# TestV2.net
KiCad netlist of a schematic drawn in EAGLE
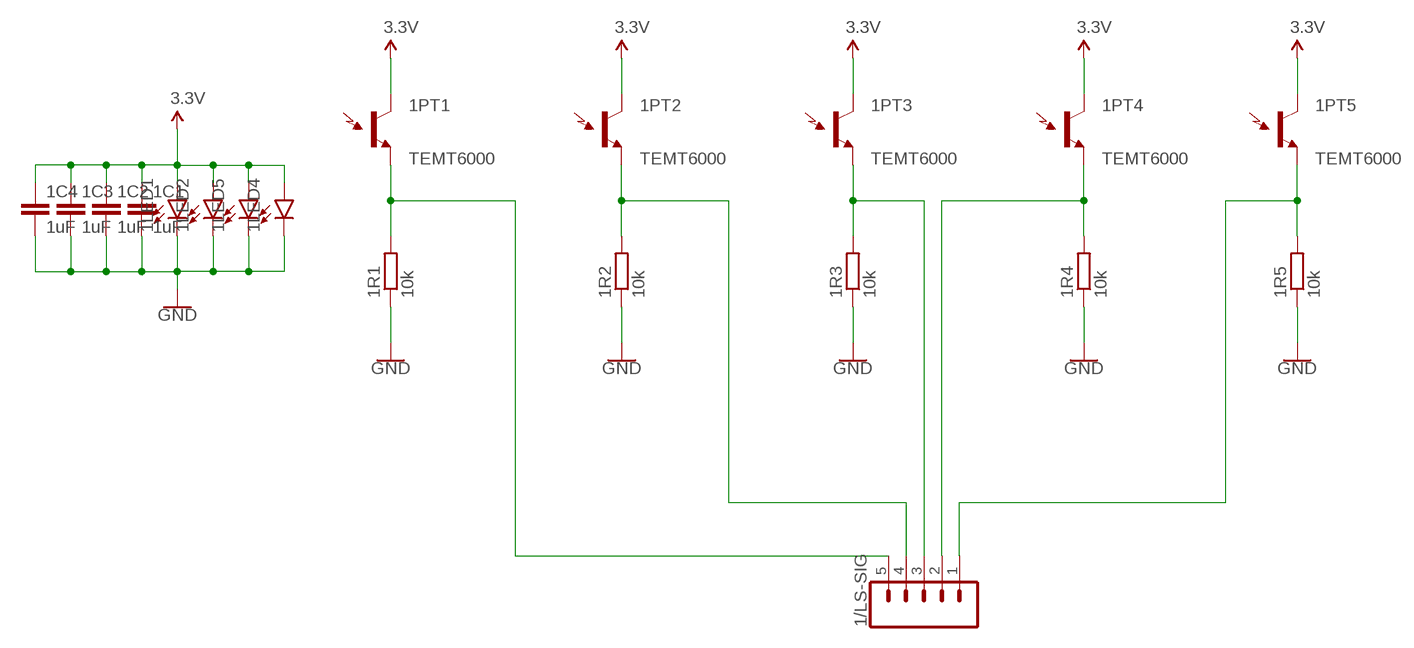
[diagram p0: schematic, sheet 1]
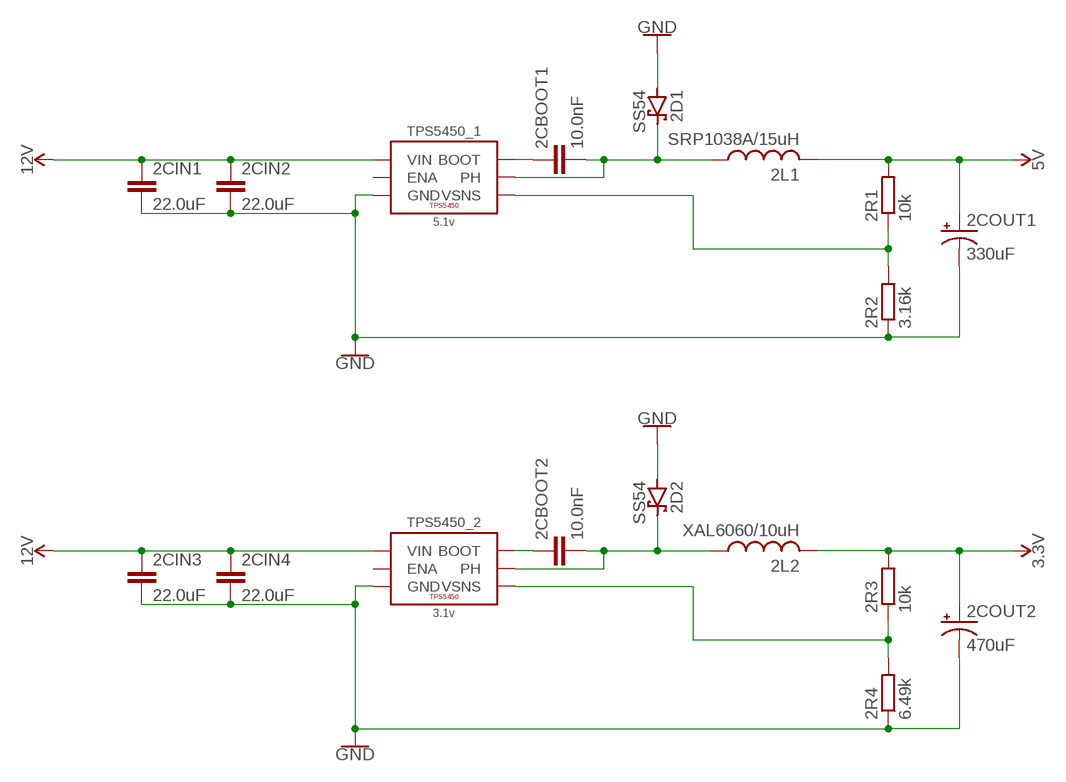
[diagram p1: schematic, sheet 2]
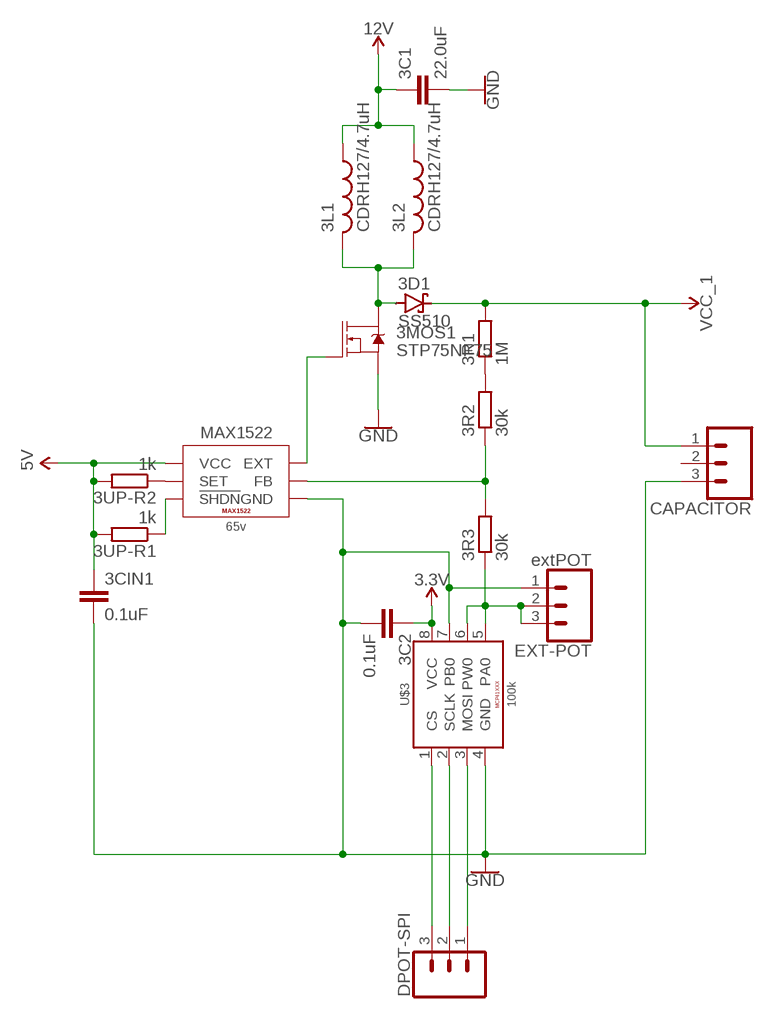
[diagram p2: schematic, sheet 3]
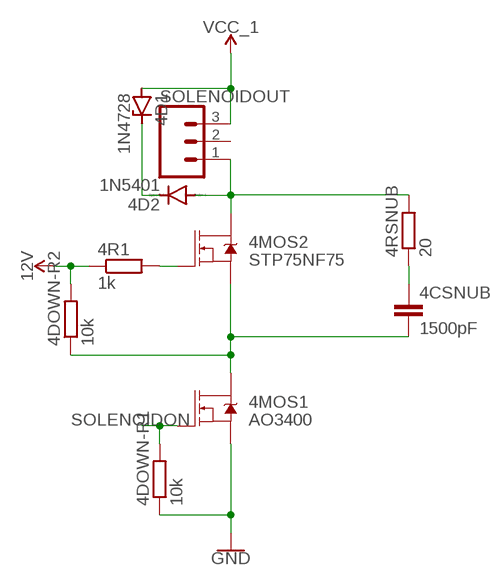
[diagram p3: schematic, sheet 4]
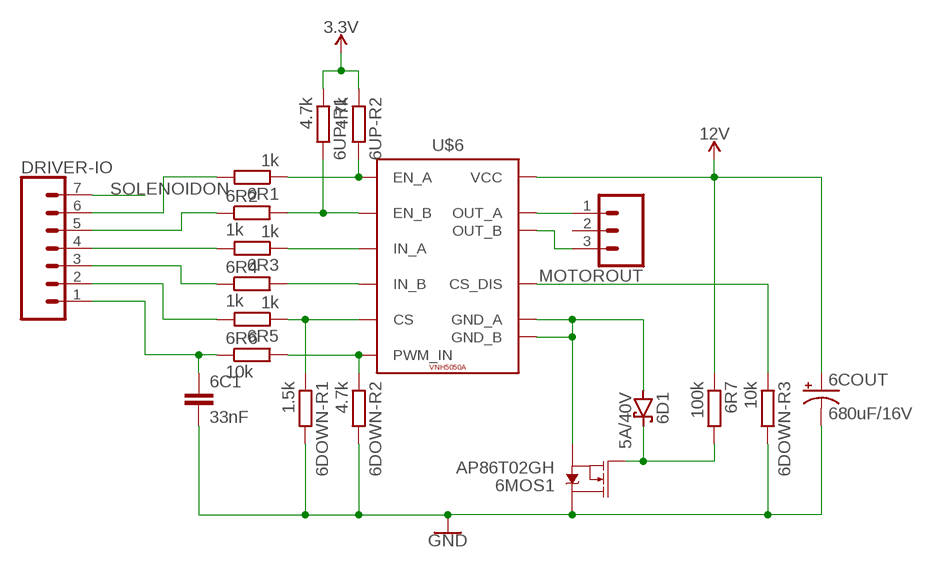
[diagram p4: schematic, sheet 5]
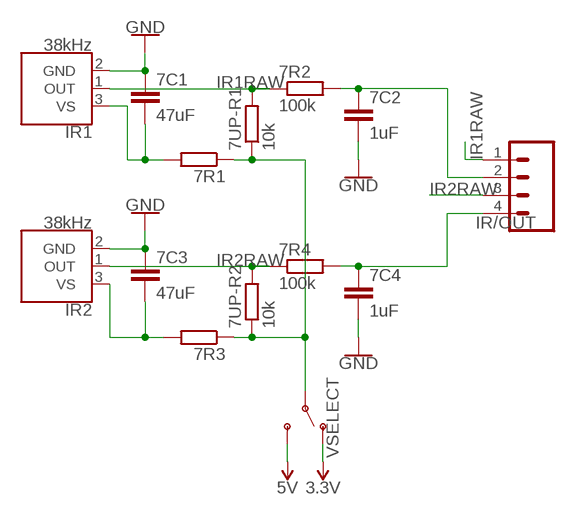
[diagram p5: schematic, sheet 6]
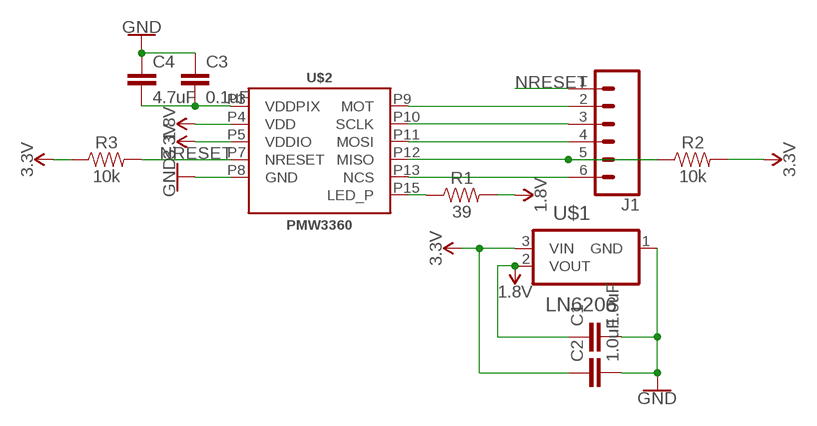
[diagram p6: schematic, sheet 7]
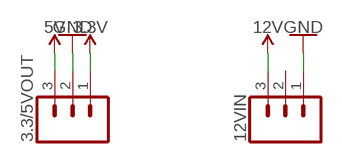
[diagram p7: schematic, sheet 8]

(export (version "E")
  (design (tool "Eeschema 10.0.6"))
  (components
    (comp (ref "1/LS-SIG")
      (value "CONN_05LOCK")
      (footprint "eagle-import:1X05_LOCK")
      (libsource (lib "eagle-import") (part "CONN_05LOCK"))
    )
    (comp (ref "1C1")
      (value "1uF")
      (footprint "eagle-import:C0603")
      (libsource (lib "eagle-import") (part "C-EUC0603"))
    )
    (comp (ref "1C2")
      (value "1uF")
      (footprint "eagle-import:C0603")
      (libsource (lib "eagle-import") (part "C-EUC0603"))
    )
    (comp (ref "1C3")
      (value "1uF")
      (footprint "eagle-import:C0603")
      (libsource (lib "eagle-import") (part "C-EUC0603"))
    )
    (comp (ref "1C4")
      (value "1uF")
      (footprint "eagle-import:C0603")
      (libsource (lib "eagle-import") (part "C-EUC0603"))
    )
    (comp (ref "1LED1")
      (value "3528LED")
      (footprint "eagle-import:3528")
      (libsource (lib "eagle-import") (part "3528LED"))
    )
    (comp (ref "1LED2")
      (value "3528LED")
      (footprint "eagle-import:3528")
      (libsource (lib "eagle-import") (part "3528LED"))
    )
    (comp (ref "1LED4")
      (value "3528LED")
      (footprint "eagle-import:3528")
      (libsource (lib "eagle-import") (part "3528LED"))
    )
    (comp (ref "1LED5")
      (value "3528LED")
      (footprint "eagle-import:3528")
      (libsource (lib "eagle-import") (part "3528LED"))
    )
    (comp (ref "1PT1")
      (value "TEMT6000")
      (footprint "eagle-import:TEMT6000")
      (libsource (lib "eagle-import") (part "LIGHT_SENSORTEMT6000"))
    )
    (comp (ref "1PT2")
      (value "TEMT6000")
      (footprint "eagle-import:TEMT6000")
      (libsource (lib "eagle-import") (part "LIGHT_SENSORTEMT6000"))
    )
    (comp (ref "1PT3")
      (value "TEMT6000")
      (footprint "eagle-import:TEMT6000")
      (libsource (lib "eagle-import") (part "LIGHT_SENSORTEMT6000"))
    )
    (comp (ref "1PT4")
      (value "TEMT6000")
      (footprint "eagle-import:TEMT6000")
      (libsource (lib "eagle-import") (part "LIGHT_SENSORTEMT6000"))
    )
    (comp (ref "1PT5")
      (value "TEMT6000")
      (footprint "eagle-import:TEMT6000")
      (libsource (lib "eagle-import") (part "LIGHT_SENSORTEMT6000"))
    )
    (comp (ref "1R1")
      (value "10k")
      (footprint "eagle-import:R0603")
      (libsource (lib "eagle-import") (part "R-EU_R0603"))
    )
    (comp (ref "1R2")
      (value "10k")
      (footprint "eagle-import:R0603")
      (libsource (lib "eagle-import") (part "R-EU_R0603"))
    )
    (comp (ref "1R3")
      (value "10k")
      (footprint "eagle-import:R0603")
      (libsource (lib "eagle-import") (part "R-EU_R0603"))
    )
    (comp (ref "1R4")
      (value "10k")
      (footprint "eagle-import:R0603")
      (libsource (lib "eagle-import") (part "R-EU_R0603"))
    )
    (comp (ref "1R5")
      (value "10k")
      (footprint "eagle-import:R0603")
      (libsource (lib "eagle-import") (part "R-EU_R0603"))
    )
    (comp (ref "4CSNUB")
      (value "1500pF")
      (footprint "eagle-import:C0603")
      (libsource (lib "eagle-import") (part "C-EUC0603"))
    )
    (comp (ref "4D1")
      (value "1N4728")
      (footprint "eagle-import:DO41Z10")
      (libsource (lib "eagle-import") (part "1N4728"))
    )
    (comp (ref "4D2")
      (value "1N5401")
      (footprint "eagle-import:DO201-15")
      (libsource (lib "eagle-import") (part "1N5400"))
    )
    (comp (ref "4DOWN-R1")
      (value "10k")
      (footprint "eagle-import:R0603")
      (libsource (lib "eagle-import") (part "R-EU_R0603"))
    )
    (comp (ref "4DOWN-R2")
      (value "10k")
      (footprint "eagle-import:R0603")
      (libsource (lib "eagle-import") (part "R-EU_R0603"))
    )
    (comp (ref "4MOS1")
      (value "AO3400")
      (footprint "eagle-import:SOT23-3")
      (libsource (lib "eagle-import") (part "MOSFET-NCH-AO3404A"))
    )
    (comp (ref "4MOS2")
      (value "STP75NF75")
      (footprint "eagle-import:TO220V")
      (libsource (lib "eagle-import") (part "MOSFET-NCH-FQP30N06L"))
    )
    (comp (ref "4R1")
      (value "1k")
      (footprint "eagle-import:R0603")
      (libsource (lib "eagle-import") (part "R-EU_R0603"))
    )
    (comp (ref "4RSNUB")
      (value "20")
      (footprint "eagle-import:R0603")
      (libsource (lib "eagle-import") (part "R-EU_R0603"))
    )
    (comp (ref "SOLENOIDOUT")
      (value "CONN_03-SCREW-5MM")
      (footprint "eagle-import:SCREWTERMINAL-5MM-3")
      (libsource (lib "eagle-import") (part "CONN_03-SCREW-5MM"))
    )
    (comp (ref "3.3/5VOUT")
      (value "CONN_03-SCREW-5MM")
      (footprint "eagle-import:SCREWTERMINAL-5MM-3")
      (libsource (lib "eagle-import") (part "CONN_03-SCREW-5MM"))
    )
    (comp (ref "12VIN")
      (value "CONN_03-SCREW-5MM")
      (footprint "eagle-import:SCREWTERMINAL-5MM-3")
      (libsource (lib "eagle-import") (part "CONN_03-SCREW-5MM"))
    )
    (comp (ref "C1")
      (value "1.0uF")
      (footprint "eagle-import:0603")
      (libsource (lib "eagle-import") (part "1.0UF-0603-16V-10%-X7R"))
    )
    (comp (ref "C2")
      (value "1.0uF")
      (footprint "eagle-import:0603")
      (libsource (lib "eagle-import") (part "1.0UF-0603-16V-10%-X7R"))
    )
    (comp (ref "C3")
      (value "0.1uF")
      (footprint "eagle-import:0603")
      (libsource (lib "eagle-import") (part "0.1UF-0603-25V-5%"))
    )
    (comp (ref "C4")
      (value "4.7uF")
      (footprint "eagle-import:0603")
      (libsource (lib "eagle-import") (part "4.7UF-0603-6.3V-(10%)"))
    )
    (comp (ref "J1")
      (value "CONN_06LOCK")
      (footprint "eagle-import:1X06_LOCK")
      (libsource (lib "eagle-import") (part "CONN_06LOCK"))
    )
    (comp (ref "R1")
      (value "39")
      (footprint "eagle-import:0603")
      (libsource (lib "eagle-import") (part "RESISTOR0603"))
    )
    (comp (ref "R2")
      (value "10k")
      (footprint "eagle-import:0603")
      (libsource (lib "eagle-import") (part "10KOHM-0603-1/10W-1%"))
    )
    (comp (ref "R3")
      (value "10k")
      (footprint "eagle-import:0603")
      (libsource (lib "eagle-import") (part "10KOHM-0603-1/10W-1%"))
    )
    (comp (ref "U$1")
      (value "LN6206")
      (footprint "eagle-import:SOT95P237X112-3N")
      (fields (field (name "MF") "Microchip") (field (name "MP") "MCP1700T-3302E/TT"))
      (libsource (lib "eagle-import") (part "MCP1700T-3302E/TT"))
    )
    (comp (ref "U$2")
      (value "PMW3360")
      (footprint "eagle-import:PMW3360")
      (libsource (lib "eagle-import") (part "PMW3360"))
    )
    (comp (ref "2CBOOT1")
      (value "10.0nF")
      (footprint "eagle-import:C0603")
      (libsource (lib "eagle-import") (part "C-EUC0603"))
    )
    (comp (ref "2CBOOT2")
      (value "10.0nF")
      (footprint "eagle-import:C0603")
      (libsource (lib "eagle-import") (part "C-EUC0603"))
    )
    (comp (ref "2CIN1")
      (value "22.0uF")
      (footprint "eagle-import:C1210")
      (libsource (lib "eagle-import") (part "C-EUC1210"))
    )
    (comp (ref "2CIN2")
      (value "22.0uF")
      (footprint "eagle-import:C1210")
      (libsource (lib "eagle-import") (part "C-EUC1210"))
    )
    (comp (ref "2CIN3")
      (value "22.0uF")
      (footprint "eagle-import:C1210")
      (libsource (lib "eagle-import") (part "C-EUC1210"))
    )
    (comp (ref "2CIN4")
      (value "22.0uF")
      (footprint "eagle-import:C1210")
      (libsource (lib "eagle-import") (part "C-EUC1210"))
    )
    (comp (ref "2COUT1")
      (value "330uF")
      (footprint "eagle-import:D_7343-31R")
      (libsource (lib "eagle-import") (part "CPOL-USD/7343-31R"))
    )
    (comp (ref "2COUT2")
      (value "470uF")
      (footprint "eagle-import:D_7343-31R")
      (libsource (lib "eagle-import") (part "CPOL-USD/7343-31R"))
    )
    (comp (ref "2D1")
      (value "SS54")
      (footprint "eagle-import:SMB")
      (libsource (lib "eagle-import") (part "SCHOTTKY-DIODESMD"))
    )
    (comp (ref "2D2")
      (value "SS54")
      (footprint "eagle-import:SMB")
      (libsource (lib "eagle-import") (part "SCHOTTKY-DIODESMD"))
    )
    (comp (ref "2L1")
      (value "SRP1038A/15uH")
      (footprint "eagle-import:SRP1038A")
      (libsource (lib "eagle-import") (part "SRP1038A"))
    )
    (comp (ref "2L2")
      (value "XAL6060/10uH")
      (footprint "eagle-import:XAL6060")
      (libsource (lib "eagle-import") (part "XAL6060"))
    )
    (comp (ref "2R1")
      (value "10k")
      (footprint "eagle-import:R0603")
      (libsource (lib "eagle-import") (part "R-EU_R0603"))
    )
    (comp (ref "2R2")
      (value "3.16k")
      (footprint "eagle-import:R0603")
      (libsource (lib "eagle-import") (part "R-EU_R0603"))
    )
    (comp (ref "2R3")
      (value "10k")
      (footprint "eagle-import:R0603")
      (libsource (lib "eagle-import") (part "R-EU_R0603"))
    )
    (comp (ref "2R4")
      (value "6.49k")
      (footprint "eagle-import:R0603")
      (libsource (lib "eagle-import") (part "R-EU_R0603"))
    )
    (comp (ref "TPS5450_1")
      (value "5.1v")
      (footprint "eagle-import:POWERPAD-SOIC-8")
      (libsource (lib "eagle-import") (part "TPS5450"))
    )
    (comp (ref "TPS5450_2")
      (value "3.1v")
      (footprint "eagle-import:POWERPAD-SOIC-8")
      (libsource (lib "eagle-import") (part "TPS5450"))
    )
    (comp (ref "3C1")
      (value "22.0uF")
      (footprint "eagle-import:C1210")
      (libsource (lib "eagle-import") (part "C-EUC1210"))
    )
    (comp (ref "3C2")
      (value "0.1uF")
      (footprint "eagle-import:C0603")
      (libsource (lib "eagle-import") (part "C-EUC0603"))
    )
    (comp (ref "3CIN1")
      (value "0.1uF")
      (footprint "eagle-import:C0603")
      (libsource (lib "eagle-import") (part "C-EUC0603"))
    )
    (comp (ref "3D1")
      (value "SS510")
      (footprint "eagle-import:SMB")
      (libsource (lib "eagle-import") (part "SCHOTTKY-DIODESMD"))
    )
    (comp (ref "3L1")
      (value "CDRH127/4.7uH")
      (footprint "eagle-import:127")
      (libsource (lib "eagle-import") (part "CDRH127"))
    )
    (comp (ref "3L2")
      (value "CDRH127/4.7uH")
      (footprint "eagle-import:127")
      (libsource (lib "eagle-import") (part "CDRH127"))
    )
    (comp (ref "3MOS1")
      (value "STP75NF75")
      (footprint "eagle-import:TO220V")
      (libsource (lib "eagle-import") (part "MOSFET-NCH-FQP30N06L"))
    )
    (comp (ref "3R1")
      (value "1M")
      (footprint "eagle-import:R0603")
      (libsource (lib "eagle-import") (part "R-EU_R0603"))
    )
    (comp (ref "3R2")
      (value "30k")
      (footprint "eagle-import:R0603")
      (libsource (lib "eagle-import") (part "R-EU_R0603"))
    )
    (comp (ref "3R3")
      (value "30k")
      (footprint "eagle-import:R0603")
      (libsource (lib "eagle-import") (part "R-EU_R0603"))
    )
    (comp (ref "3UP-R1")
      (value "1k")
      (footprint "eagle-import:R0603")
      (libsource (lib "eagle-import") (part "R-EU_R0603"))
    )
    (comp (ref "3UP-R2")
      (value "1k")
      (footprint "eagle-import:R0603")
      (libsource (lib "eagle-import") (part "R-EU_R0603"))
    )
    (comp (ref "CAPACITOR")
      (value "CONN_03-SCREW-5MM")
      (footprint "eagle-import:SCREWTERMINAL-5MM-3")
      (libsource (lib "eagle-import") (part "CONN_03-SCREW-5MM"))
    )
    (comp (ref "DPOT-SPI")
      (value "CONN_03LOCK")
      (footprint "eagle-import:1X03_LOCK")
      (libsource (lib "eagle-import") (part "CONN_03LOCK"))
    )
    (comp (ref "EXT-POT")
      (value "extPOT")
      (footprint "eagle-import:1X03")
      (libsource (lib "eagle-import") (part "CONN_03"))
    )
    (comp (ref "MAX1522")
      (value "65v")
      (footprint "eagle-import:SOT23-6")
      (fields (field (name "MANUFACTURER_PART_NUMBER") "MAX1522EUT+T"))
      (libsource (lib "eagle-import") (part "MAX1522EUT+T"))
    )
    (comp (ref "U$3")
      (value "100k")
      (footprint "eagle-import:SOIC-8")
      (libsource (lib "eagle-import") (part "MCP41XXX"))
    )
    (comp (ref "6C1")
      (value "33nF")
      (footprint "eagle-import:C0603")
      (libsource (lib "eagle-import") (part "C-EUC0603"))
    )
    (comp (ref "6COUT")
      (value "680uF/16V")
      (footprint "eagle-import:E3,5-8")
      (libsource (lib "eagle-import") (part "CPOL-USE3.5-8"))
    )
    (comp (ref "6D1")
      (value "5A/40V")
      (footprint "eagle-import:SMB")
      (libsource (lib "eagle-import") (part "SCHOTTKY-DIODESMD"))
    )
    (comp (ref "6DOWN-R1")
      (value "1.5k")
      (footprint "eagle-import:R0603")
      (libsource (lib "eagle-import") (part "R-EU_R0603"))
    )
    (comp (ref "6DOWN-R2")
      (value "4.7k")
      (footprint "eagle-import:R0603")
      (libsource (lib "eagle-import") (part "R-EU_R0603"))
    )
    (comp (ref "6DOWN-R3")
      (value "10k")
      (footprint "eagle-import:R0603")
      (libsource (lib "eagle-import") (part "R-EU_R0603"))
    )
    (comp (ref "6MOS1")
      (value "AP86T02GH")
      (footprint "eagle-import:DPAK")
      (libsource (lib "eagle-import") (part "MOSFET-NCH-FDD8780"))
    )
    (comp (ref "6R1")
      (value "1k")
      (footprint "eagle-import:R0603")
      (libsource (lib "eagle-import") (part "R-EU_R0603"))
    )
    (comp (ref "6R2")
      (value "1k")
      (footprint "eagle-import:R0603")
      (libsource (lib "eagle-import") (part "R-EU_R0603"))
    )
    (comp (ref "6R3")
      (value "1k")
      (footprint "eagle-import:R0603")
      (libsource (lib "eagle-import") (part "R-EU_R0603"))
    )
    (comp (ref "6R4")
      (value "1k")
      (footprint "eagle-import:R0603")
      (libsource (lib "eagle-import") (part "R-EU_R0603"))
    )
    (comp (ref "6R5")
      (value "1k")
      (footprint "eagle-import:R0603")
      (libsource (lib "eagle-import") (part "R-EU_R0603"))
    )
    (comp (ref "6R6")
      (value "10k")
      (footprint "eagle-import:R0603")
      (libsource (lib "eagle-import") (part "R-EU_R0603"))
    )
    (comp (ref "6R7")
      (value "100k")
      (footprint "eagle-import:R0603")
      (libsource (lib "eagle-import") (part "R-EU_R0603"))
    )
    (comp (ref "6UP-R1")
      (value "4.7k")
      (footprint "eagle-import:R0603")
      (libsource (lib "eagle-import") (part "R-EU_R0603"))
    )
    (comp (ref "6UP-R2")
      (value "4.7k")
      (footprint "eagle-import:R0603")
      (libsource (lib "eagle-import") (part "R-EU_R0603"))
    )
    (comp (ref "DRIVER-IO")
      (value "CONN_07LOCK")
      (footprint "eagle-import:1X07_LOCK")
      (libsource (lib "eagle-import") (part "CONN_07LOCK"))
    )
    (comp (ref "MOTOROUT")
      (value "CONN_03-SCREW-5MM")
      (footprint "eagle-import:SCREWTERMINAL-5MM-3")
      (libsource (lib "eagle-import") (part "CONN_03-SCREW-5MM"))
    )
    (comp (ref "U$6")
      (value "VNH5050A")
      (footprint "eagle-import:POWERSSO-36")
      (libsource (lib "eagle-import") (part "VNH5050A"))
    )
    (comp (ref "7C1")
      (value "47uF")
      (footprint "eagle-import:C0603")
      (libsource (lib "eagle-import") (part "C-EUC0603"))
    )
    (comp (ref "7C2")
      (value "1uF")
      (footprint "eagle-import:C0603")
      (libsource (lib "eagle-import") (part "C-EUC0603"))
    )
    (comp (ref "7C3")
      (value "47uF")
      (footprint "eagle-import:C0603")
      (libsource (lib "eagle-import") (part "C-EUC0603"))
    )
    (comp (ref "7C4")
      (value "1uF")
      (footprint "eagle-import:C0603")
      (libsource (lib "eagle-import") (part "C-EUC0603"))
    )
    (comp (ref "7R1")
      (value "R-EU_R0603")
      (footprint "eagle-import:R0603")
      (libsource (lib "eagle-import") (part "R-EU_R0603"))
    )
    (comp (ref "7R2")
      (value "100k")
      (footprint "eagle-import:R0603")
      (libsource (lib "eagle-import") (part "R-EU_R0603"))
    )
    (comp (ref "7R3")
      (value "R-EU_R0603")
      (footprint "eagle-import:R0603")
      (libsource (lib "eagle-import") (part "R-EU_R0603"))
    )
    (comp (ref "7R4")
      (value "100k")
      (footprint "eagle-import:R0603")
      (libsource (lib "eagle-import") (part "R-EU_R0603"))
    )
    (comp (ref "7UP-R1")
      (value "10k")
      (footprint "eagle-import:R0603")
      (libsource (lib "eagle-import") (part "R-EU_R0603"))
    )
    (comp (ref "7UP-R2")
      (value "10k")
      (footprint "eagle-import:R0603")
      (libsource (lib "eagle-import") (part "R-EU_R0603"))
    )
    (comp (ref "IR/OUT")
      (value "CONN_04LOCK")
      (footprint "eagle-import:1X04_LOCK")
      (libsource (lib "eagle-import") (part "CONN_04LOCK"))
    )
    (comp (ref "IR1")
      (value "38kHz")
      (footprint "eagle-import:TSOP382")
      (libsource (lib "eagle-import") (part "TSOP38238"))
    )
    (comp (ref "IR2")
      (value "38kHz")
      (footprint "eagle-import:TSOP382")
      (libsource (lib "eagle-import") (part "TSOP38238"))
    )
    (comp (ref "VSELECT")
      (value "SWITCH-SPDT-PTH-11.6X4.0MM-LOCK")
      (footprint "eagle-import:SWITCH_SPDT_PTH_11.6X4.0MM_LOCK")
      (libsource (lib "eagle-import") (part "SWITCH-SPDT-PTH-11.6X4.0MM-LOCK"))
    )
  )
  (nets
    (net (code "1") (name "1.8V") (class "Default")
      (node (ref "C1") (pin "1") (pinfunction "1_1") (pintype "passive"))
      (node (ref "R1") (pin "2") (pinfunction "2_2") (pintype "passive"))
      (node (ref "U$1") (pin "2") (pinfunction "VOUT_2") (pintype "output"))
      (node (ref "U$2") (pin "P4") (pinfunction "VDD_P4") (pintype "power_in"))
    )
    (net (code "2") (name "3.3V") (class "Default")
      (node (ref "1C1") (pin "1") (pinfunction "1_1") (pintype "passive"))
      (node (ref "1C2") (pin "1") (pinfunction "1_1") (pintype "passive"))
      (node (ref "1C3") (pin "1") (pinfunction "1_1") (pintype "passive"))
      (node (ref "1C4") (pin "1") (pinfunction "1_1") (pintype "passive"))
      (node (ref "1LED1") (pin "A") (pinfunction "A_A") (pintype "passive"))
      (node (ref "1LED2") (pin "A") (pinfunction "A_A") (pintype "passive"))
      (node (ref "1LED4") (pin "A") (pinfunction "A_A") (pintype "passive"))
      (node (ref "1LED5") (pin "A") (pinfunction "A_A") (pintype "passive"))
      (node (ref "1PT1") (pin "COLLECTOR") (pinfunction "C1_COLLECTOR") (pintype "passive"))
      (node (ref "1PT2") (pin "COLLECTOR") (pinfunction "C1_COLLECTOR") (pintype "passive"))
      (node (ref "1PT3") (pin "COLLECTOR") (pinfunction "C1_COLLECTOR") (pintype "passive"))
      (node (ref "1PT4") (pin "COLLECTOR") (pinfunction "C1_COLLECTOR") (pintype "passive"))
      (node (ref "1PT5") (pin "COLLECTOR") (pinfunction "C1_COLLECTOR") (pintype "passive"))
      (node (ref "2COUT2") (pin "+") (pinfunction "+_+") (pintype "passive"))
      (node (ref "2L2") (pin "2") (pinfunction "2_2") (pintype "passive"))
      (node (ref "2R3") (pin "2") (pinfunction "2_2") (pintype "passive"))
      (node (ref "3.3/5VOUT") (pin "1") (pinfunction "1_1") (pintype "passive"))
      (node (ref "3C2") (pin "1") (pinfunction "1_1") (pintype "passive"))
      (node (ref "6UP-R1") (pin "1") (pinfunction "1_1") (pintype "passive"))
      (node (ref "6UP-R2") (pin "1") (pinfunction "1_1") (pintype "passive"))
      (node (ref "C2") (pin "1") (pinfunction "1_1") (pintype "passive"))
      (node (ref "R2") (pin "2") (pinfunction "2_2") (pintype "passive"))
      (node (ref "R3") (pin "1") (pinfunction "1_1") (pintype "passive"))
      (node (ref "U$1") (pin "3") (pinfunction "VIN_3") (pintype "input"))
      (node (ref "U$2") (pin "P5") (pinfunction "VDDIO_P5") (pintype "power_in"))
      (node (ref "U$3") (pin "8") (pinfunction "VCC_8") (pintype "power_in"))
      (node (ref "VSELECT") (pin "1") (pinfunction "O_1") (pintype "passive"))
    )
    (net (code "3") (name "5V") (class "Default")
      (node (ref "2COUT1") (pin "+") (pinfunction "+_+") (pintype "passive"))
      (node (ref "2L1") (pin "2") (pinfunction "2_2") (pintype "passive"))
      (node (ref "2R1") (pin "2") (pinfunction "2_2") (pintype "passive"))
      (node (ref "3.3/5VOUT") (pin "3") (pinfunction "3_3") (pintype "passive"))
      (node (ref "3CIN1") (pin "1") (pinfunction "1_1") (pintype "passive"))
      (node (ref "3UP-R1") (pin "2") (pinfunction "2_2") (pintype "passive"))
      (node (ref "3UP-R2") (pin "2") (pinfunction "2_2") (pintype "passive"))
      (node (ref "MAX1522") (pin "6") (pinfunction "VCC_6") (pintype "power_in"))
      (node (ref "VSELECT") (pin "3") (pinfunction "S_3") (pintype "passive"))
    )
    (net (code "4") (name "12V") (class "Default")
      (node (ref "12VIN") (pin "3") (pinfunction "3_3") (pintype "passive"))
      (node (ref "2CIN1") (pin "1") (pinfunction "1_1") (pintype "passive"))
      (node (ref "2CIN2") (pin "1") (pinfunction "1_1") (pintype "passive"))
      (node (ref "2CIN3") (pin "1") (pinfunction "1_1") (pintype "passive"))
      (node (ref "2CIN4") (pin "1") (pinfunction "1_1") (pintype "passive"))
      (node (ref "3C1") (pin "1") (pinfunction "1_1") (pintype "passive"))
      (node (ref "3L1") (pin "1") (pinfunction "1_1") (pintype "passive"))
      (node (ref "3L2") (pin "1") (pinfunction "1_1") (pintype "passive"))
      (node (ref "4DOWN-R2") (pin "2") (pinfunction "2_2") (pintype "passive"))
      (node (ref "4R1") (pin "1") (pinfunction "1_1") (pintype "passive"))
      (node (ref "6COUT") (pin "+") (pinfunction "+_+") (pintype "passive"))
      (node (ref "6R7") (pin "1") (pinfunction "1_1") (pintype "passive"))
      (node (ref "TPS5450_1") (pin "7") (pinfunction "VIN_7") (pintype "power_in"))
      (node (ref "TPS5450_2") (pin "7") (pinfunction "VIN_7") (pintype "power_in"))
      (node (ref "U$6") (pin "1") (pinfunction "VCC_1") (pintype "power_in"))
      (node (ref "U$6") (pin "P$13") (pinfunction "VCC_P$13") (pintype "power_in"))
      (node (ref "U$6") (pin "P$14") (pinfunction "VCC_P$14") (pintype "power_in"))
      (node (ref "U$6") (pin "P$15") (pinfunction "VCC_P$15") (pintype "power_in"))
      (node (ref "U$6") (pin "P$16") (pinfunction "VCC_P$16") (pintype "power_in"))
      (node (ref "U$6") (pin "P$17") (pinfunction "VCC_P$17") (pintype "power_in"))
      (node (ref "U$6") (pin "P$18") (pinfunction "VCC_P$18") (pintype "power_in"))
      (node (ref "U$6") (pin "P$19") (pinfunction "VCC_P$19") (pintype "power_in"))
      (node (ref "U$6") (pin "P$20") (pinfunction "VCC_P$20") (pintype "power_in"))
      (node (ref "U$6") (pin "P$21") (pinfunction "VCC_P$21") (pintype "power_in"))
      (node (ref "U$6") (pin "P$22") (pinfunction "VCC_P$22") (pintype "power_in"))
      (node (ref "U$6") (pin "P$23") (pinfunction "VCC_P$23") (pintype "power_in"))
      (node (ref "U$6") (pin "P$24") (pinfunction "VCC_P$24") (pintype "power_in"))
      (node (ref "U$6") (pin "P13") (pinfunction "VCC_P13") (pintype "power_in"))
      (node (ref "U$6") (pin "P24") (pinfunction "VCC_P24") (pintype "power_in"))
    )
    (net (code "5") (name "GND") (class "Default")
      (node (ref "12VIN") (pin "1") (pinfunction "1_1") (pintype "passive"))
      (node (ref "1C1") (pin "2") (pinfunction "2_2") (pintype "passive"))
      (node (ref "1C2") (pin "2") (pinfunction "2_2") (pintype "passive"))
      (node (ref "1C3") (pin "2") (pinfunction "2_2") (pintype "passive"))
      (node (ref "1C4") (pin "2") (pinfunction "2_2") (pintype "passive"))
      (node (ref "1LED1") (pin "C") (pinfunction "C_C") (pintype "passive"))
      (node (ref "1LED2") (pin "C") (pinfunction "C_C") (pintype "passive"))
      (node (ref "1LED4") (pin "C") (pinfunction "C_C") (pintype "passive"))
      (node (ref "1LED5") (pin "C") (pinfunction "C_C") (pintype "passive"))
      (node (ref "1R1") (pin "1") (pinfunction "1_1") (pintype "passive"))
      (node (ref "1R2") (pin "1") (pinfunction "1_1") (pintype "passive"))
      (node (ref "1R3") (pin "1") (pinfunction "1_1") (pintype "passive"))
      (node (ref "1R4") (pin "1") (pinfunction "1_1") (pintype "passive"))
      (node (ref "1R5") (pin "1") (pinfunction "1_1") (pintype "passive"))
      (node (ref "2CIN1") (pin "2") (pinfunction "2_2") (pintype "passive"))
      (node (ref "2CIN2") (pin "2") (pinfunction "2_2") (pintype "passive"))
      (node (ref "2CIN3") (pin "2") (pinfunction "2_2") (pintype "passive"))
      (node (ref "2CIN4") (pin "2") (pinfunction "2_2") (pintype "passive"))
      (node (ref "2COUT1") (pin "-") (pinfunction "-_-") (pintype "passive"))
      (node (ref "2COUT2") (pin "-") (pinfunction "-_-") (pintype "passive"))
      (node (ref "2D1") (pin "A") (pinfunction "A_A") (pintype "passive"))
      (node (ref "2D2") (pin "A") (pinfunction "A_A") (pintype "passive"))
      (node (ref "2R2") (pin "1") (pinfunction "1_1") (pintype "passive"))
      (node (ref "2R4") (pin "1") (pinfunction "1_1") (pintype "passive"))
      (node (ref "3.3/5VOUT") (pin "2") (pinfunction "2_2") (pintype "passive"))
      (node (ref "3C1") (pin "2") (pinfunction "2_2") (pintype "passive"))
      (node (ref "3C2") (pin "2") (pinfunction "2_2") (pintype "passive"))
      (node (ref "3CIN1") (pin "2") (pinfunction "2_2") (pintype "passive"))
      (node (ref "3MOS1") (pin "3") (pinfunction "S_3") (pintype "bidirectional"))
      (node (ref "4DOWN-R1") (pin "1") (pinfunction "1_1") (pintype "passive"))
      (node (ref "4MOS1") (pin "2") (pinfunction "S_2") (pintype "bidirectional"))
      (node (ref "6C1") (pin "2") (pinfunction "2_2") (pintype "passive"))
      (node (ref "6COUT") (pin "-") (pinfunction "-_-") (pintype "passive"))
      (node (ref "6DOWN-R1") (pin "2") (pinfunction "2_2") (pintype "passive"))
      (node (ref "6DOWN-R2") (pin "2") (pinfunction "2_2") (pintype "passive"))
      (node (ref "6DOWN-R3") (pin "2") (pinfunction "2_2") (pintype "passive"))
      (node (ref "6MOS1") (pin "4") (pinfunction "D_4") (pintype "bidirectional"))
      (node (ref "7C1") (pin "1") (pinfunction "1_1") (pintype "passive"))
      (node (ref "7C2") (pin "2") (pinfunction "2_2") (pintype "passive"))
      (node (ref "7C3") (pin "1") (pinfunction "1_1") (pintype "passive"))
      (node (ref "7C4") (pin "2") (pinfunction "2_2") (pintype "passive"))
      (node (ref "C1") (pin "2") (pinfunction "2_2") (pintype "passive"))
      (node (ref "C2") (pin "2") (pinfunction "2_2") (pintype "passive"))
      (node (ref "C3") (pin "1") (pinfunction "1_1") (pintype "passive"))
      (node (ref "C4") (pin "1") (pinfunction "1_1") (pintype "passive"))
      (node (ref "CAPACITOR") (pin "3") (pinfunction "3_3") (pintype "passive"))
      (node (ref "EXT-POT") (pin "1") (pinfunction "1_1") (pintype "passive"))
      (node (ref "IR1") (pin "2") (pinfunction "GND_2") (pintype "bidirectional"))
      (node (ref "IR2") (pin "2") (pinfunction "GND_2") (pintype "bidirectional"))
      (node (ref "MAX1522") (pin "1") (pinfunction "GND_1") (pintype "power_in"))
      (node (ref "TPS5450_1") (pin "6") (pinfunction "GND_6") (pintype "power_in"))
      (node (ref "TPS5450_1") (pin "9") (pinfunction "GND_9") (pintype "power_in"))
      (node (ref "TPS5450_1") (pin "P$1") (pinfunction "GND_P$1") (pintype "power_in"))
      (node (ref "TPS5450_1") (pin "P$2") (pinfunction "GND_P$2") (pintype "power_in"))
      (node (ref "TPS5450_1") (pin "P$3") (pinfunction "GND_P$3") (pintype "power_in"))
      (node (ref "TPS5450_1") (pin "P$4") (pinfunction "GND_P$4") (pintype "power_in"))
      (node (ref "TPS5450_1") (pin "P$5") (pinfunction "GND_P$5") (pintype "power_in"))
      (node (ref "TPS5450_1") (pin "P$6") (pinfunction "GND_P$6") (pintype "power_in"))
      (node (ref "TPS5450_2") (pin "6") (pinfunction "GND_6") (pintype "power_in"))
      (node (ref "TPS5450_2") (pin "9") (pinfunction "GND_9") (pintype "power_in"))
      (node (ref "TPS5450_2") (pin "P$1") (pinfunction "GND_P$1") (pintype "power_in"))
      (node (ref "TPS5450_2") (pin "P$2") (pinfunction "GND_P$2") (pintype "power_in"))
      (node (ref "TPS5450_2") (pin "P$3") (pinfunction "GND_P$3") (pintype "power_in"))
      (node (ref "TPS5450_2") (pin "P$4") (pinfunction "GND_P$4") (pintype "power_in"))
      (node (ref "TPS5450_2") (pin "P$5") (pinfunction "GND_P$5") (pintype "power_in"))
      (node (ref "TPS5450_2") (pin "P$6") (pinfunction "GND_P$6") (pintype "power_in"))
      (node (ref "U$1") (pin "1") (pinfunction "GND_1") (pintype "power_in"))
      (node (ref "U$2") (pin "P8") (pinfunction "GND_P8") (pintype "power_in"))
      (node (ref "U$3") (pin "4") (pinfunction "GND_4") (pintype "power_in"))
      (node (ref "U$3") (pin "7") (pinfunction "PB0_7") (pintype "bidirectional"))
    )
    (net (code "6") (name "IR1RAW") (class "Default")
      (node (ref "7R2") (pin "1") (pinfunction "1_1") (pintype "passive"))
      (node (ref "7UP-R1") (pin "2") (pinfunction "2_2") (pintype "passive"))
      (node (ref "IR/OUT") (pin "1") (pinfunction "1_1") (pintype "passive"))
      (node (ref "IR1") (pin "1") (pinfunction "OUT_1") (pintype "bidirectional"))
    )
    (net (code "7") (name "IR2RAW") (class "Default")
      (node (ref "7R4") (pin "1") (pinfunction "1_1") (pintype "passive"))
      (node (ref "7UP-R2") (pin "2") (pinfunction "2_2") (pintype "passive"))
      (node (ref "IR/OUT") (pin "3") (pinfunction "3_3") (pintype "passive"))
      (node (ref "IR2") (pin "1") (pinfunction "OUT_1") (pintype "bidirectional"))
    )
    (net (code "8") (name "NRESET") (class "Default")
      (node (ref "J1") (pin "1") (pinfunction "1_1") (pintype "passive"))
      (node (ref "R3") (pin "2") (pinfunction "2_2") (pintype "passive"))
      (node (ref "U$2") (pin "P7") (pinfunction "NRESET_P7") (pintype "input"))
    )
    (net (code "9") (name "Net-(1PT1-E1)") (class "Default")
      (node (ref "1/LS-SIG") (pin "5") (pinfunction "5_5") (pintype "passive"))
      (node (ref "1PT1") (pin "EMITTER") (pinfunction "E1_EMITTER") (pintype "passive"))
      (node (ref "1R1") (pin "2") (pinfunction "2_2") (pintype "passive"))
    )
    (net (code "10") (name "Net-(1PT2-E1)") (class "Default")
      (node (ref "1/LS-SIG") (pin "4") (pinfunction "4_4") (pintype "passive"))
      (node (ref "1PT2") (pin "EMITTER") (pinfunction "E1_EMITTER") (pintype "passive"))
      (node (ref "1R2") (pin "2") (pinfunction "2_2") (pintype "passive"))
    )
    (net (code "11") (name "Net-(1PT3-E1)") (class "Default")
      (node (ref "1/LS-SIG") (pin "3") (pinfunction "3_3") (pintype "passive"))
      (node (ref "1PT3") (pin "EMITTER") (pinfunction "E1_EMITTER") (pintype "passive"))
      (node (ref "1R3") (pin "2") (pinfunction "2_2") (pintype "passive"))
    )
    (net (code "12") (name "Net-(1PT4-E1)") (class "Default")
      (node (ref "1/LS-SIG") (pin "2") (pinfunction "2_2") (pintype "passive"))
      (node (ref "1PT4") (pin "EMITTER") (pinfunction "E1_EMITTER") (pintype "passive"))
      (node (ref "1R4") (pin "2") (pinfunction "2_2") (pintype "passive"))
    )
    (net (code "13") (name "Net-(1PT5-E1)") (class "Default")
      (node (ref "1/LS-SIG") (pin "1") (pinfunction "1_1") (pintype "passive"))
      (node (ref "1PT5") (pin "EMITTER") (pinfunction "E1_EMITTER") (pintype "passive"))
      (node (ref "1R5") (pin "2") (pinfunction "2_2") (pintype "passive"))
    )
    (net (code "14") (name "Net-(3MOS1-D)") (class "Default")
      (node (ref "3D1") (pin "A") (pinfunction "A_A") (pintype "passive"))
      (node (ref "3L1") (pin "2") (pinfunction "2_2") (pintype "passive"))
      (node (ref "3L2") (pin "2") (pinfunction "2_2") (pintype "passive"))
      (node (ref "3MOS1") (pin "2") (pinfunction "D_2") (pintype "bidirectional"))
    )
    (net (code "15") (name "Net-(3MOS1-G)") (class "Default")
      (node (ref "3MOS1") (pin "1") (pinfunction "G_1") (pintype "bidirectional"))
      (node (ref "MAX1522") (pin "5") (pinfunction "EXT_5") (pintype "output"))
    )
    (net (code "16") (name "Net-(3R1-Pad1)") (class "Default")
      (node (ref "3R1") (pin "1") (pinfunction "1_1") (pintype "passive"))
      (node (ref "3R2") (pin "2") (pinfunction "2_2") (pintype "passive"))
    )
    (net (code "17") (name "Net-(4CSNUB-Pad1)") (class "Default")
      (node (ref "4CSNUB") (pin "1") (pinfunction "1_1") (pintype "passive"))
      (node (ref "4RSNUB") (pin "1") (pinfunction "1_1") (pintype "passive"))
    )
    (net (code "18") (name "Net-(4D1-PadC)") (class "Default")
      (node (ref "4D1") (pin "C") (pinfunction "C_C") (pintype "passive"))
      (node (ref "4D2") (pin "C") (pinfunction "C_C") (pintype "passive"))
    )
    (net (code "19") (name "Net-(4MOS1-D)") (class "Default")
      (node (ref "4CSNUB") (pin "2") (pinfunction "2_2") (pintype "passive"))
      (node (ref "4DOWN-R2") (pin "1") (pinfunction "1_1") (pintype "passive"))
      (node (ref "4MOS1") (pin "3") (pinfunction "D_3") (pintype "bidirectional"))
      (node (ref "4MOS2") (pin "3") (pinfunction "S_3") (pintype "bidirectional"))
    )
    (net (code "20") (name "Net-(4MOS2-D)") (class "Default")
      (node (ref "4D2") (pin "A") (pinfunction "A_A") (pintype "passive"))
      (node (ref "4MOS2") (pin "2") (pinfunction "D_2") (pintype "bidirectional"))
      (node (ref "4RSNUB") (pin "2") (pinfunction "2_2") (pintype "passive"))
      (node (ref "SOLENOIDOUT") (pin "1") (pinfunction "1_1") (pintype "passive"))
    )
    (net (code "21") (name "Net-(4MOS2-G)") (class "Default")
      (node (ref "4MOS2") (pin "1") (pinfunction "G_1") (pintype "bidirectional"))
      (node (ref "4R1") (pin "2") (pinfunction "2_2") (pintype "passive"))
    )
    (net (code "22") (name "Net-(6C1-Pad1)") (class "Default")
      (node (ref "6C1") (pin "1") (pinfunction "1_1") (pintype "passive"))
      (node (ref "6R6") (pin "1") (pinfunction "1_1") (pintype "passive"))
      (node (ref "DRIVER-IO") (pin "1") (pinfunction "1_1") (pintype "passive"))
    )
    (net (code "23") (name "Net-(6MOS1-G)") (class "Default")
      (node (ref "6D1") (pin "C") (pinfunction "C_C") (pintype "passive"))
      (node (ref "6MOS1") (pin "1") (pinfunction "G_1") (pintype "bidirectional"))
      (node (ref "6R7") (pin "2") (pinfunction "2_2") (pintype "passive"))
    )
    (net (code "24") (name "Net-(6MOS1-S)") (class "Default")
      (node (ref "6D1") (pin "A") (pinfunction "A_A") (pintype "passive"))
      (node (ref "6MOS1") (pin "3") (pinfunction "S_3") (pintype "bidirectional"))
      (node (ref "U$6") (pin "P1") (pinfunction "GND_A_P1") (pintype "output"))
      (node (ref "U$6") (pin "P3") (pinfunction "GND_A_P3") (pintype "output"))
      (node (ref "U$6") (pin "P30") (pinfunction "GND_B_P30") (pintype "output"))
      (node (ref "U$6") (pin "P31") (pinfunction "GND_B_P31") (pintype "output"))
      (node (ref "U$6") (pin "P32") (pinfunction "GND_B_P32") (pintype "output"))
      (node (ref "U$6") (pin "P33") (pinfunction "GND_B_P33") (pintype "output"))
      (node (ref "U$6") (pin "P34") (pinfunction "GND_B_P34") (pintype "output"))
      (node (ref "U$6") (pin "P36") (pinfunction "GND_B_P36") (pintype "output"))
      (node (ref "U$6") (pin "P4") (pinfunction "GND_A_P4") (pintype "output"))
      (node (ref "U$6") (pin "P5") (pinfunction "GND_A_P5") (pintype "output"))
      (node (ref "U$6") (pin "P6") (pinfunction "GND_A_P6") (pintype "output"))
      (node (ref "U$6") (pin "P7") (pinfunction "GND_A_P7") (pintype "output"))
    )
    (net (code "25") (name "Net-(6R1-Pad2)") (class "Default")
      (node (ref "6R1") (pin "2") (pinfunction "2_2") (pintype "passive"))
      (node (ref "DRIVER-IO") (pin "6") (pinfunction "6_6") (pintype "passive"))
    )
    (net (code "26") (name "Net-(6R2-Pad1)") (class "Default")
      (node (ref "6R2") (pin "1") (pinfunction "1_1") (pintype "passive"))
      (node (ref "DRIVER-IO") (pin "5") (pinfunction "5_5") (pintype "passive"))
    )
    (net (code "27") (name "Net-(6R3-Pad2)") (class "Default")
      (node (ref "6R3") (pin "2") (pinfunction "2_2") (pintype "passive"))
      (node (ref "DRIVER-IO") (pin "4") (pinfunction "4_4") (pintype "passive"))
    )
    (net (code "28") (name "Net-(6R4-Pad1)") (class "Default")
      (node (ref "6R4") (pin "1") (pinfunction "1_1") (pintype "passive"))
      (node (ref "DRIVER-IO") (pin "3") (pinfunction "3_3") (pintype "passive"))
    )
    (net (code "29") (name "Net-(6R5-Pad2)") (class "Default")
      (node (ref "6R5") (pin "2") (pinfunction "2_2") (pintype "passive"))
      (node (ref "DRIVER-IO") (pin "2") (pinfunction "2_2") (pintype "passive"))
    )
    (net (code "30") (name "Net-(7C2-Pad1)") (class "Default")
      (node (ref "7C2") (pin "1") (pinfunction "1_1") (pintype "passive"))
      (node (ref "7R2") (pin "2") (pinfunction "2_2") (pintype "passive"))
      (node (ref "IR/OUT") (pin "2") (pinfunction "2_2") (pintype "passive"))
    )
    (net (code "31") (name "Net-(7C4-Pad1)") (class "Default")
      (node (ref "7C4") (pin "1") (pinfunction "1_1") (pintype "passive"))
      (node (ref "7R4") (pin "2") (pinfunction "2_2") (pintype "passive"))
      (node (ref "IR/OUT") (pin "4") (pinfunction "4_4") (pintype "passive"))
    )
    (net (code "32") (name "Net-(IR1-VS)") (class "Default")
      (node (ref "7C1") (pin "2") (pinfunction "2_2") (pintype "passive"))
      (node (ref "7R1") (pin "2") (pinfunction "2_2") (pintype "passive"))
      (node (ref "IR1") (pin "3") (pinfunction "VS_3") (pintype "bidirectional"))
    )
    (net (code "33") (name "Net-(IR2-VS)") (class "Default")
      (node (ref "7C3") (pin "2") (pinfunction "2_2") (pintype "passive"))
      (node (ref "7R3") (pin "2") (pinfunction "2_2") (pintype "passive"))
      (node (ref "IR2") (pin "3") (pinfunction "VS_3") (pintype "bidirectional"))
    )
    (net (code "34") (name "Net-(MAX1522-FB)") (class "Default")
      (node (ref "3R2") (pin "1") (pinfunction "1_1") (pintype "passive"))
      (node (ref "3R3") (pin "2") (pinfunction "2_2") (pintype "passive"))
      (node (ref "MAX1522") (pin "2") (pinfunction "FB_2") (pintype "input"))
    )
    (net (code "35") (name "Net-(MAX1522-SET)") (class "Default")
      (node (ref "3UP-R2") (pin "1") (pinfunction "1_1") (pintype "passive"))
      (node (ref "MAX1522") (pin "3") (pinfunction "SET_3") (pintype "input"))
    )
    (net (code "36") (name "Net-(MAX1522-~{SHDN})") (class "Default")
      (node (ref "3UP-R1") (pin "1") (pinfunction "1_1") (pintype "passive"))
      (node (ref "MAX1522") (pin "4") (pinfunction "~{SHDN}_4") (pintype "input"))
    )
    (net (code "37") (name "Net-(MOTOROUT-Pad1)") (class "Default")
      (node (ref "MOTOROUT") (pin "1") (pinfunction "1_1") (pintype "passive"))
      (node (ref "U$6") (pin "2") (pinfunction "OUT_A_2") (pintype "output"))
      (node (ref "U$6") (pin "P$10") (pinfunction "OUT_A_P$10") (pintype "output"))
      (node (ref "U$6") (pin "P$11") (pinfunction "OUT_A_P$11") (pintype "output"))
      (node (ref "U$6") (pin "P$12") (pinfunction "OUT_A_P$12") (pintype "output"))
      (node (ref "U$6") (pin "P$7") (pinfunction "OUT_A_P$7") (pintype "output"))
      (node (ref "U$6") (pin "P$8") (pinfunction "OUT_A_P$8") (pintype "output"))
      (node (ref "U$6") (pin "P$9") (pinfunction "OUT_A_P$9") (pintype "output"))
      (node (ref "U$6") (pin "P10") (pinfunction "OUT_A_P10") (pintype "output"))
      (node (ref "U$6") (pin "P11") (pinfunction "OUT_A_P11") (pintype "output"))
      (node (ref "U$6") (pin "P12") (pinfunction "OUT_A_P12") (pintype "output"))
      (node (ref "U$6") (pin "P14") (pinfunction "OUT_A_P14") (pintype "output"))
      (node (ref "U$6") (pin "P2") (pinfunction "OUT_A_P2") (pintype "output"))
      (node (ref "U$6") (pin "P8") (pinfunction "OUT_A_P8") (pintype "output"))
      (node (ref "U$6") (pin "P9") (pinfunction "OUT_A_P9") (pintype "output"))
    )
    (net (code "38") (name "Net-(MOTOROUT-Pad3)") (class "Default")
      (node (ref "MOTOROUT") (pin "3") (pinfunction "3_3") (pintype "passive"))
      (node (ref "U$6") (pin "3") (pinfunction "OUT_B_3") (pintype "output"))
      (node (ref "U$6") (pin "P$1") (pinfunction "OUT_B_P$1") (pintype "output"))
      (node (ref "U$6") (pin "P$2") (pinfunction "OUT_B_P$2") (pintype "output"))
      (node (ref "U$6") (pin "P$3") (pinfunction "OUT_B_P$3") (pintype "output"))
      (node (ref "U$6") (pin "P$4") (pinfunction "OUT_B_P$4") (pintype "output"))
      (node (ref "U$6") (pin "P$5") (pinfunction "OUT_B_P$5") (pintype "output"))
      (node (ref "U$6") (pin "P$6") (pinfunction "OUT_B_P$6") (pintype "output"))
      (node (ref "U$6") (pin "P23") (pinfunction "OUT_B_P23") (pintype "output"))
      (node (ref "U$6") (pin "P25") (pinfunction "OUT_B_P25") (pintype "output"))
      (node (ref "U$6") (pin "P26") (pinfunction "OUT_B_P26") (pintype "output"))
      (node (ref "U$6") (pin "P27") (pinfunction "OUT_B_P27") (pintype "output"))
      (node (ref "U$6") (pin "P28") (pinfunction "OUT_B_P28") (pintype "output"))
      (node (ref "U$6") (pin "P29") (pinfunction "OUT_B_P29") (pintype "output"))
      (node (ref "U$6") (pin "P35") (pinfunction "OUT_B_P35") (pintype "output"))
    )
    (net (code "39") (name "Net-(TPS5450_1-BOOT)") (class "Default")
      (node (ref "2CBOOT1") (pin "1") (pinfunction "1_1") (pintype "passive"))
      (node (ref "TPS5450_1") (pin "1") (pinfunction "BOOT_1") (pintype "bidirectional"))
    )
    (net (code "40") (name "Net-(TPS5450_1-PH)") (class "Default")
      (node (ref "2CBOOT1") (pin "2") (pinfunction "2_2") (pintype "passive"))
      (node (ref "2D1") (pin "C") (pinfunction "C_C") (pintype "passive"))
      (node (ref "2L1") (pin "1") (pinfunction "1_1") (pintype "passive"))
      (node (ref "TPS5450_1") (pin "8") (pinfunction "PH_8") (pintype "bidirectional"))
    )
    (net (code "41") (name "Net-(TPS5450_1-VSNS)") (class "Default")
      (node (ref "2R1") (pin "1") (pinfunction "1_1") (pintype "passive"))
      (node (ref "2R2") (pin "2") (pinfunction "2_2") (pintype "passive"))
      (node (ref "TPS5450_1") (pin "4") (pinfunction "VSNS_4") (pintype "input"))
    )
    (net (code "42") (name "Net-(TPS5450_2-BOOT)") (class "Default")
      (node (ref "2CBOOT2") (pin "1") (pinfunction "1_1") (pintype "passive"))
      (node (ref "TPS5450_2") (pin "1") (pinfunction "BOOT_1") (pintype "bidirectional"))
    )
    (net (code "43") (name "Net-(TPS5450_2-PH)") (class "Default")
      (node (ref "2CBOOT2") (pin "2") (pinfunction "2_2") (pintype "passive"))
      (node (ref "2D2") (pin "C") (pinfunction "C_C") (pintype "passive"))
      (node (ref "2L2") (pin "1") (pinfunction "1_1") (pintype "passive"))
      (node (ref "TPS5450_2") (pin "8") (pinfunction "PH_8") (pintype "bidirectional"))
    )
    (net (code "44") (name "Net-(TPS5450_2-VSNS)") (class "Default")
      (node (ref "2R3") (pin "1") (pinfunction "1_1") (pintype "passive"))
      (node (ref "2R4") (pin "2") (pinfunction "2_2") (pintype "passive"))
      (node (ref "TPS5450_2") (pin "4") (pinfunction "VSNS_4") (pintype "input"))
    )
    (net (code "45") (name "Net-(U$2-LED_P)") (class "Default")
      (node (ref "R1") (pin "1") (pinfunction "1_1") (pintype "passive"))
      (node (ref "U$2") (pin "P15") (pinfunction "LED_P_P15") (pintype "input"))
    )
    (net (code "46") (name "Net-(U$2-MISO)") (class "Default")
      (node (ref "J1") (pin "5") (pinfunction "5_5") (pintype "passive"))
      (node (ref "R2") (pin "1") (pinfunction "1_1") (pintype "passive"))
      (node (ref "U$2") (pin "P12") (pinfunction "MISO_P12") (pintype "output"))
    )
    (net (code "47") (name "Net-(U$2-MOSI)") (class "Default")
      (node (ref "J1") (pin "4") (pinfunction "4_4") (pintype "passive"))
      (node (ref "U$2") (pin "P11") (pinfunction "MOSI_P11") (pintype "input"))
    )
    (net (code "48") (name "Net-(U$2-MOT)") (class "Default")
      (node (ref "J1") (pin "2") (pinfunction "2_2") (pintype "passive"))
      (node (ref "U$2") (pin "P9") (pinfunction "MOT_P9") (pintype "output"))
    )
    (net (code "49") (name "Net-(U$2-NCS)") (class "Default")
      (node (ref "J1") (pin "6") (pinfunction "6_6") (pintype "passive"))
      (node (ref "U$2") (pin "P13") (pinfunction "NCS_P13") (pintype "input"))
    )
    (net (code "50") (name "Net-(U$2-SCLK)") (class "Default")
      (node (ref "J1") (pin "3") (pinfunction "3_3") (pintype "passive"))
      (node (ref "U$2") (pin "P10") (pinfunction "SCLK_P10") (pintype "input"))
    )
    (net (code "51") (name "Net-(U$2-VDDPIX)") (class "Default")
      (node (ref "C3") (pin "2") (pinfunction "2_2") (pintype "passive"))
      (node (ref "C4") (pin "2") (pinfunction "2_2") (pintype "passive"))
      (node (ref "U$2") (pin "P3") (pinfunction "VDDPIX_P3") (pintype "power_in"))
    )
    (net (code "52") (name "Net-(U$3-CS)") (class "Default")
      (node (ref "DPOT-SPI") (pin "3") (pinfunction "3_3") (pintype "passive"))
      (node (ref "U$3") (pin "1") (pinfunction "CS_1") (pintype "input"))
    )
    (net (code "53") (name "Net-(U$3-MOSI)") (class "Default")
      (node (ref "DPOT-SPI") (pin "1") (pinfunction "1_1") (pintype "passive"))
      (node (ref "U$3") (pin "3") (pinfunction "MOSI_3") (pintype "input"))
    )
    (net (code "54") (name "Net-(U$3-PA0)") (class "Default")
      (node (ref "3R3") (pin "1") (pinfunction "1_1") (pintype "passive"))
      (node (ref "EXT-POT") (pin "2") (pinfunction "2_2") (pintype "passive"))
      (node (ref "EXT-POT") (pin "3") (pinfunction "3_3") (pintype "passive"))
      (node (ref "U$3") (pin "5") (pinfunction "PA0_5") (pintype "bidirectional"))
      (node (ref "U$3") (pin "6") (pinfunction "PW0_6") (pintype "bidirectional"))
    )
    (net (code "55") (name "Net-(U$3-SCLK)") (class "Default")
      (node (ref "DPOT-SPI") (pin "2") (pinfunction "2_2") (pintype "passive"))
      (node (ref "U$3") (pin "2") (pinfunction "SCLK_2") (pintype "input"))
    )
    (net (code "56") (name "Net-(U$6-CS)") (class "Default")
      (node (ref "6DOWN-R1") (pin "1") (pinfunction "1_1") (pintype "passive"))
      (node (ref "6R5") (pin "1") (pinfunction "1_1") (pintype "passive"))
      (node (ref "U$6") (pin "P19") (pinfunction "CS_P19") (pintype "output"))
    )
    (net (code "57") (name "Net-(U$6-CS_DIS)") (class "Default")
      (node (ref "6DOWN-R3") (pin "1") (pinfunction "1_1") (pintype "passive"))
      (node (ref "U$6") (pin "P20") (pinfunction "CS_DIS_P20") (pintype "bidirectional"))
    )
    (net (code "58") (name "Net-(U$6-EN_A)") (class "Default")
      (node (ref "6R1") (pin "1") (pinfunction "1_1") (pintype "passive"))
      (node (ref "6UP-R2") (pin "2") (pinfunction "2_2") (pintype "passive"))
      (node (ref "U$6") (pin "P16") (pinfunction "EN_A_P16") (pintype "bidirectional"))
    )
    (net (code "59") (name "Net-(U$6-EN_B)") (class "Default")
      (node (ref "6R2") (pin "2") (pinfunction "2_2") (pintype "passive"))
      (node (ref "6UP-R1") (pin "2") (pinfunction "2_2") (pintype "passive"))
      (node (ref "U$6") (pin "P21") (pinfunction "EN_B_P21") (pintype "bidirectional"))
    )
    (net (code "60") (name "Net-(U$6-IN_A)") (class "Default")
      (node (ref "6R3") (pin "1") (pinfunction "1_1") (pintype "passive"))
      (node (ref "U$6") (pin "P15") (pinfunction "IN_A_P15") (pintype "input"))
    )
    (net (code "61") (name "Net-(U$6-IN_B)") (class "Default")
      (node (ref "6R4") (pin "2") (pinfunction "2_2") (pintype "passive"))
      (node (ref "U$6") (pin "P22") (pinfunction "IN_B_P22") (pintype "input"))
    )
    (net (code "62") (name "Net-(U$6-PWM_IN)") (class "Default")
      (node (ref "6DOWN-R2") (pin "1") (pinfunction "1_1") (pintype "passive"))
      (node (ref "6R6") (pin "2") (pinfunction "2_2") (pintype "passive"))
      (node (ref "U$6") (pin "P17") (pinfunction "PWM_IN_P17") (pintype "input"))
    )
    (net (code "63") (name "Net-(VSELECT-P)") (class "Default")
      (node (ref "7R1") (pin "1") (pinfunction "1_1") (pintype "passive"))
      (node (ref "7R3") (pin "1") (pinfunction "1_1") (pintype "passive"))
      (node (ref "7UP-R1") (pin "1") (pinfunction "1_1") (pintype "passive"))
      (node (ref "7UP-R2") (pin "1") (pinfunction "1_1") (pintype "passive"))
      (node (ref "VSELECT") (pin "2") (pinfunction "P_2") (pintype "passive"))
    )
    (net (code "64") (name "SOLENOIDON") (class "Default")
      (node (ref "4DOWN-R1") (pin "2") (pinfunction "2_2") (pintype "passive"))
      (node (ref "4MOS1") (pin "1") (pinfunction "G_1") (pintype "bidirectional"))
      (node (ref "DRIVER-IO") (pin "7") (pinfunction "7_7") (pintype "passive"))
    )
    (net (code "65") (name "VCC_1") (class "Default")
      (node (ref "3D1") (pin "C") (pinfunction "C_C") (pintype "passive"))
      (node (ref "3R1") (pin "2") (pinfunction "2_2") (pintype "passive"))
      (node (ref "4D1") (pin "A") (pinfunction "A_A") (pintype "passive"))
      (node (ref "CAPACITOR") (pin "1") (pinfunction "1_1") (pintype "passive"))
      (node (ref "SOLENOIDOUT") (pin "3") (pinfunction "3_3") (pintype "passive"))
    )
    (net (code "66") (name "unconnected-(12VIN-Pad2)") (class "Default")
      (node (ref "12VIN") (pin "2") (pinfunction "2_2") (pintype "passive"))
    )
    (net (code "67") (name "unconnected-(CAPACITOR-Pad2)") (class "Default")
      (node (ref "CAPACITOR") (pin "2") (pinfunction "2_2") (pintype "passive"))
    )
    (net (code "68") (name "unconnected-(MOTOROUT-Pad2)") (class "Default")
      (node (ref "MOTOROUT") (pin "2") (pinfunction "2_2") (pintype "passive"))
    )
    (net (code "69") (name "unconnected-(SOLENOIDOUT-Pad2)") (class "Default")
      (node (ref "SOLENOIDOUT") (pin "2") (pinfunction "2_2") (pintype "passive"))
    )
    (net (code "70") (name "unconnected-(TPS5450_1-ENA-Pad5)") (class "Default")
      (node (ref "TPS5450_1") (pin "5") (pinfunction "ENA_5") (pintype "input"))
    )
    (net (code "71") (name "unconnected-(TPS5450_1-NC-Pad2)") (class "Default")
      (node (ref "TPS5450_1") (pin "2") (pinfunction "NC_2") (pintype "no_connect"))
    )
    (net (code "72") (name "unconnected-(TPS5450_1-NC-Pad3)") (class "Default")
      (node (ref "TPS5450_1") (pin "3") (pinfunction "NC_3") (pintype "no_connect"))
    )
    (net (code "73") (name "unconnected-(TPS5450_2-ENA-Pad5)") (class "Default")
      (node (ref "TPS5450_2") (pin "5") (pinfunction "ENA_5") (pintype "input"))
    )
    (net (code "74") (name "unconnected-(TPS5450_2-NC-Pad2)") (class "Default")
      (node (ref "TPS5450_2") (pin "2") (pinfunction "NC_2") (pintype "no_connect"))
    )
    (net (code "75") (name "unconnected-(TPS5450_2-NC-Pad3)") (class "Default")
      (node (ref "TPS5450_2") (pin "3") (pinfunction "NC_3") (pintype "no_connect"))
    )
    (net (code "76") (name "unconnected-(U$2-P$1-PadP1)") (class "Default")
      (node (ref "U$2") (pin "P1") (pinfunction "P$1_P1") (pintype "no_connect"))
    )
    (net (code "77") (name "unconnected-(U$2-P$1-PadP2)") (class "Default")
      (node (ref "U$2") (pin "P2") (pinfunction "P$1_P2") (pintype "no_connect"))
    )
    (net (code "78") (name "unconnected-(U$2-P$1-PadP6)") (class "Default")
      (node (ref "U$2") (pin "P6") (pinfunction "P$1_P6") (pintype "no_connect"))
    )
    (net (code "79") (name "unconnected-(U$2-P$1-PadP14)") (class "Default")
      (node (ref "U$2") (pin "P14") (pinfunction "P$1_P14") (pintype "no_connect"))
    )
    (net (code "80") (name "unconnected-(U$2-P$1-PadP16)") (class "Default")
      (node (ref "U$2") (pin "P16") (pinfunction "P$1_P16") (pintype "no_connect"))
    )
    (net (code "81") (name "unconnected-(U$6-NC-PadP18)") (class "Default")
      (node (ref "U$6") (pin "P18") (pinfunction "NC_P18") (pintype "no_connect"))
    )
  )
)
